# Texas.net
KiCad netlist of a schematic drawn in EAGLE
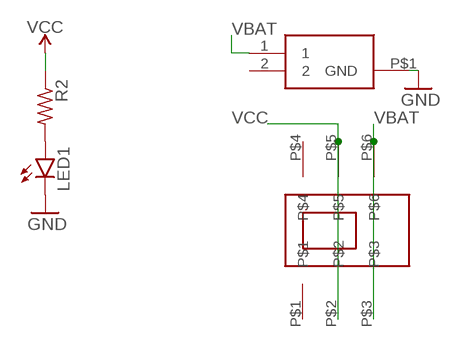
[diagram p0: schematic, sheet 1]

(export (version "E")
  (design (tool "Eeschema 10.0.6"))
  (components
    (comp (ref "LED1")
      (value "LEDCHIP-LED0805")
      (footprint "eagle-import:CHIP-LED0805")
      (libsource (lib "eagle-import") (part "LEDCHIP-LED0805"))
    )
    (comp (ref "R2")
      (value "R-US_R0603")
      (footprint "eagle-import:R0603")
      (libsource (lib "eagle-import") (part "R-US_R0603"))
    )
    (comp (ref "U$1")
      (value "CL-SB-22A-02T-SLIDE-SWITCH-TUCKED-PADS")
      (footprint "eagle-import:CL-SB-22A-02T-DPDT-COMPACT-SWITCH")
      (libsource (lib "eagle-import") (part "CL-SB-22A-02T-SLIDE-SWITCH-TUCKED-PADS"))
    )
    (comp (ref "VBAT")
      (value "BAT-HLD-012-SMT")
      (footprint "eagle-import:BATHLD012SMT")
      (fields (field (name "MOUSER_PART_NUMBER") "712-BAT-HLD-012-SMT"))
      (libsource (lib "eagle-import") (part "BAT-HLD-012-SMT"))
    )
  )
  (nets
    (net (code "1") (name "/VBAT") (class "Default")
      (node (ref "U$1") (pin "P$3") (pinfunction "P$3_P$3") (pintype "bidirectional"))
      (node (ref "U$1") (pin "P$6") (pinfunction "P$6_P$6") (pintype "bidirectional"))
      (node (ref "VBAT") (pin "1") (pinfunction "1_1") (pintype "bidirectional"))
    )
    (net (code "2") (name "GND") (class "Default")
      (node (ref "LED1") (pin "C") (pinfunction "C_C") (pintype "passive"))
      (node (ref "VBAT") (pin "P$1") (pinfunction "GND_P$1") (pintype "bidirectional"))
    )
    (net (code "3") (name "Net-(LED1-PadA)") (class "Default")
      (node (ref "LED1") (pin "A") (pinfunction "A_A") (pintype "passive"))
      (node (ref "R2") (pin "2") (pinfunction "2_2") (pintype "passive"))
    )
    (net (code "4") (name "VCC") (class "Default")
      (node (ref "R2") (pin "1") (pinfunction "1_1") (pintype "passive"))
      (node (ref "U$1") (pin "P$2") (pinfunction "P$2_P$2") (pintype "bidirectional"))
      (node (ref "U$1") (pin "P$5") (pinfunction "P$5_P$5") (pintype "bidirectional"))
    )
    (net (code "5") (name "unconnected-(U$1-PadP$1)") (class "Default")
      (node (ref "U$1") (pin "P$1") (pinfunction "P$1_P$1") (pintype "bidirectional"))
    )
    (net (code "6") (name "unconnected-(U$1-PadP$4)") (class "Default")
      (node (ref "U$1") (pin "P$4") (pinfunction "P$4_P$4") (pintype "bidirectional"))
    )
    (net (code "7") (name "unconnected-(VBAT-Pad2)") (class "Default")
      (node (ref "VBAT") (pin "2") (pinfunction "2_2") (pintype "bidirectional"))
    )
  )
)
